# v1_0.net
KiCad netlist of a schematic drawn in Altium Designer
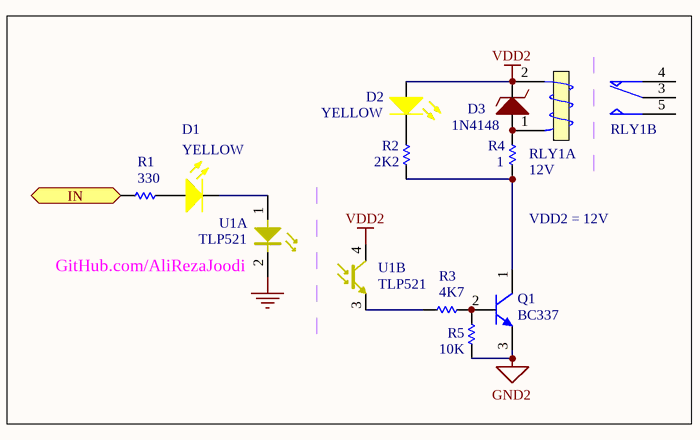
[diagram p0: v1.0.SchDoc]

(export (version "E")
  (design (tool "Eeschema 10.0.6"))
  (components
    (comp (ref "D1")
      (value "YELLOW")
      (footprint "LED_THD_3MM_YELLOW_R")
      (description "LED, Yellow")
      (fields (field (name "MANUFACTURER") "Generic Components") (field (name "PUBLISHER") "Altium Limited"))
      (libsource (lib "Display") (part "LED_YELLOW"))
    )
    (comp (ref "D2")
      (value "YELLOW")
      (footprint "LED_THD_3MM_YELLOW_R")
      (description "LED, Yellow")
      (fields (field (name "MANUFACTURER") "Generic Components") (field (name "PUBLISHER") "Altium Limited"))
      (libsource (lib "Display") (part "LED_YELLOW"))
    )
    (comp (ref "D3")
      (value "1N4148")
      (footprint "D_THD_AXIAL0.3_DO-35")
      (description "Diode, Zener")
      (libsource (lib "Passive") (part "Diode_Zener"))
    )
    (comp (ref "Q1")
      (value "BC337")
      (footprint "TO92C")
      (description "NPN Bipolar Transistor")
      (fields (field (name "MANUFACTURER") "Generic Components") (field (name "PUBLISHER") "Altium Limited"))
      (libsource (lib "Miscellaneous Devices") (part "NPN"))
    )
    (comp (ref "R1")
      (value "330")
      (footprint "R_THD_AXIAL0.4(1/4W)")
      (description "Resistor")
      (libsource (lib "Passive") (part "Resistor"))
    )
    (comp (ref "R2")
      (value "2K2")
      (footprint "R_THD_AXIAL0.4(1/4W)")
      (description "Resistor")
      (libsource (lib "Passive") (part "Resistor"))
    )
    (comp (ref "R3")
      (value "4K7")
      (footprint "R_THD_AXIAL0.4(1/4W)")
      (description "Resistor")
      (libsource (lib "Passive") (part "Resistor"))
    )
    (comp (ref "R4")
      (value "1")
      (footprint "R_THD_AXIAL0.4(1/4W)")
      (description "Resistor")
      (libsource (lib "Passive") (part "Resistor"))
    )
    (comp (ref "R5")
      (value "10K")
      (footprint "R_THD_AXIAL0.4(1/4W)")
      (description "Resistor")
      (libsource (lib "Passive") (part "Resistor"))
    )
    (comp (ref "RLY1")
      (value "12V")
      (footprint "RELAY_SPDT_5PIN_2216")
      (description "SPDT Relay")
      (libsource (lib "Passive") (part "Relay_SPDT_2Form"))
    )
    (comp (ref "U1")
      (value "TLP521")
      (footprint "DIP_4")
      (description "Optoisolator")
      (fields (field (name "PUBLISHER") "Altium Limited"))
      (libsource (lib "IC") (part "Optoisolator"))
    )
  )
  (nets
    (net (code "1") (name "/IN") (class "Default")
      (node (ref "R1") (pin "2") (pinfunction "2_2") (pintype "passive"))
    )
    (net (code "2") (name "GND") (class "Default")
      (node (ref "U1") (pin "2") (pinfunction "K_2") (pintype "power_in"))
    )
    (net (code "3") (name "GND2") (class "Default")
      (node (ref "Q1") (pin "3") (pinfunction "E_3") (pintype "passive"))
      (node (ref "R5") (pin "2") (pinfunction "2_2") (pintype "passive"))
    )
    (net (code "4") (name "Net-(D1-A)") (class "Default")
      (node (ref "D1") (pin "1") (pinfunction "A_1") (pintype "passive"))
      (node (ref "R1") (pin "1") (pinfunction "1_1") (pintype "passive"))
    )
    (net (code "5") (name "Net-(D1-K)") (class "Default")
      (node (ref "D1") (pin "2") (pinfunction "K_2") (pintype "passive"))
      (node (ref "U1") (pin "1") (pinfunction "A_1") (pintype "power_in"))
    )
    (net (code "6") (name "Net-(D2-K)") (class "Default")
      (node (ref "D2") (pin "2") (pinfunction "K_2") (pintype "passive"))
      (node (ref "R2") (pin "2") (pinfunction "2_2") (pintype "passive"))
    )
    (net (code "7") (name "Net-(Q1-B)") (class "Default")
      (node (ref "Q1") (pin "2") (pinfunction "B_2") (pintype "passive"))
      (node (ref "R3") (pin "1") (pinfunction "1_1") (pintype "passive"))
      (node (ref "R5") (pin "1") (pinfunction "1_1") (pintype "passive"))
    )
    (net (code "8") (name "Net-(Q1-C)") (class "Default")
      (node (ref "Q1") (pin "1") (pinfunction "C_1") (pintype "passive"))
      (node (ref "R2") (pin "1") (pinfunction "1_1") (pintype "passive"))
      (node (ref "R4") (pin "1") (pinfunction "1_1") (pintype "passive"))
    )
    (net (code "9") (name "Net-(RLY1A-T2)") (class "Default")
      (node (ref "D3") (pin "1") (pinfunction "1_1") (pintype "passive"))
      (node (ref "R4") (pin "2") (pinfunction "2_2") (pintype "passive"))
      (node (ref "RLY1") (pin "1") (pinfunction "T2_1") (pintype "passive"))
    )
    (net (code "10") (name "Net-(U1B-E)") (class "Default")
      (node (ref "R3") (pin "2") (pinfunction "2_2") (pintype "passive"))
      (node (ref "U1") (pin "3") (pinfunction "E_3") (pintype "passive"))
    )
    (net (code "11") (name "VDD2") (class "Default")
      (node (ref "D2") (pin "1") (pinfunction "A_1") (pintype "passive"))
      (node (ref "D3") (pin "2") (pinfunction "2_2") (pintype "passive"))
      (node (ref "RLY1") (pin "2") (pinfunction "T1_2") (pintype "passive"))
      (node (ref "U1") (pin "4") (pinfunction "C_4") (pintype "passive"))
    )
    (net (code "12") (name "unconnected-(RLY1B-COM-Pad3)") (class "Default")
      (node (ref "RLY1") (pin "3") (pinfunction "COM_3") (pintype "passive"))
    )
    (net (code "13") (name "unconnected-(RLY1B-NC-Pad4)") (class "Default")
      (node (ref "RLY1") (pin "4") (pinfunction "NC_4") (pintype "passive"))
    )
    (net (code "14") (name "unconnected-(RLY1B-NO-Pad5)") (class "Default")
      (node (ref "RLY1") (pin "5") (pinfunction "NO_5") (pintype "passive"))
    )
  )
)
